# attiny85_pogo_pgm.net
KiCad netlist of a schematic drawn in EAGLE
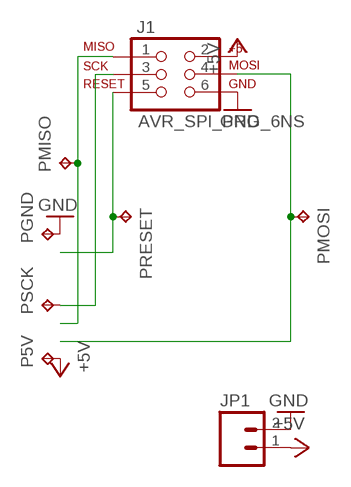
[diagram p0: schematic, sheet 1]

(export (version "E")
  (design (tool "Eeschema 10.0.6"))
  (components
    (comp (ref "J1")
      (value "AVR_SPI_PRG_6NS")
      (footprint "eagle-import:2X3-NS")
      (libsource (lib "eagle-import") (part "AVR_SPI_PRG_6NS"))
    )
    (comp (ref "JP1")
      (value "M02PTH")
      (footprint "eagle-import:1X02")
      (libsource (lib "eagle-import") (part "M02PTH"))
    )
    (comp (ref "P5V")
      (value "TPTP12R")
      (footprint "eagle-import:TP12R")
      (libsource (lib "eagle-import") (part "TPTP12R"))
    )
    (comp (ref "PGND")
      (value "TPTP12R")
      (footprint "eagle-import:TP12R")
      (libsource (lib "eagle-import") (part "TPTP12R"))
    )
    (comp (ref "PMISO")
      (value "TPTP12R")
      (footprint "eagle-import:TP12R")
      (libsource (lib "eagle-import") (part "TPTP12R"))
    )
    (comp (ref "PMOSI")
      (value "TPTP12R")
      (footprint "eagle-import:TP12R")
      (libsource (lib "eagle-import") (part "TPTP12R"))
    )
    (comp (ref "PRESET")
      (value "TPTP12R")
      (footprint "eagle-import:TP12R")
      (libsource (lib "eagle-import") (part "TPTP12R"))
    )
    (comp (ref "PSCK")
      (value "TPTP12R")
      (footprint "eagle-import:TP12R")
      (libsource (lib "eagle-import") (part "TPTP12R"))
    )
  )
  (nets
    (net (code "1") (name "+5V") (class "Default")
      (node (ref "J1") (pin "2") (pinfunction "2_2") (pintype "passive"))
      (node (ref "JP1") (pin "1") (pinfunction "1_1") (pintype "passive"))
      (node (ref "P5V") (pin "TP") (pinfunction "TP_TP") (pintype "input"))
    )
    (net (code "2") (name "GND") (class "Default")
      (node (ref "J1") (pin "6") (pinfunction "6_6") (pintype "passive"))
      (node (ref "JP1") (pin "2") (pinfunction "2_2") (pintype "passive"))
      (node (ref "PGND") (pin "TP") (pinfunction "TP_TP") (pintype "input"))
    )
    (net (code "3") (name "Net-(J1-Pad1)") (class "Default")
      (node (ref "J1") (pin "1") (pinfunction "1_1") (pintype "passive"))
      (node (ref "PMISO") (pin "TP") (pinfunction "TP_TP") (pintype "input"))
    )
    (net (code "4") (name "Net-(J1-Pad3)") (class "Default")
      (node (ref "J1") (pin "3") (pinfunction "3_3") (pintype "passive"))
      (node (ref "PSCK") (pin "TP") (pinfunction "TP_TP") (pintype "input"))
    )
    (net (code "5") (name "Net-(J1-Pad4)") (class "Default")
      (node (ref "J1") (pin "4") (pinfunction "4_4") (pintype "passive"))
      (node (ref "PMOSI") (pin "TP") (pinfunction "TP_TP") (pintype "input"))
    )
    (net (code "6") (name "Net-(J1-Pad5)") (class "Default")
      (node (ref "J1") (pin "5") (pinfunction "5_5") (pintype "passive"))
      (node (ref "PRESET") (pin "TP") (pinfunction "TP_TP") (pintype "input"))
    )
  )
)
